# RK809-5.net
KiCad netlist of a schematic drawn in Altium Designer
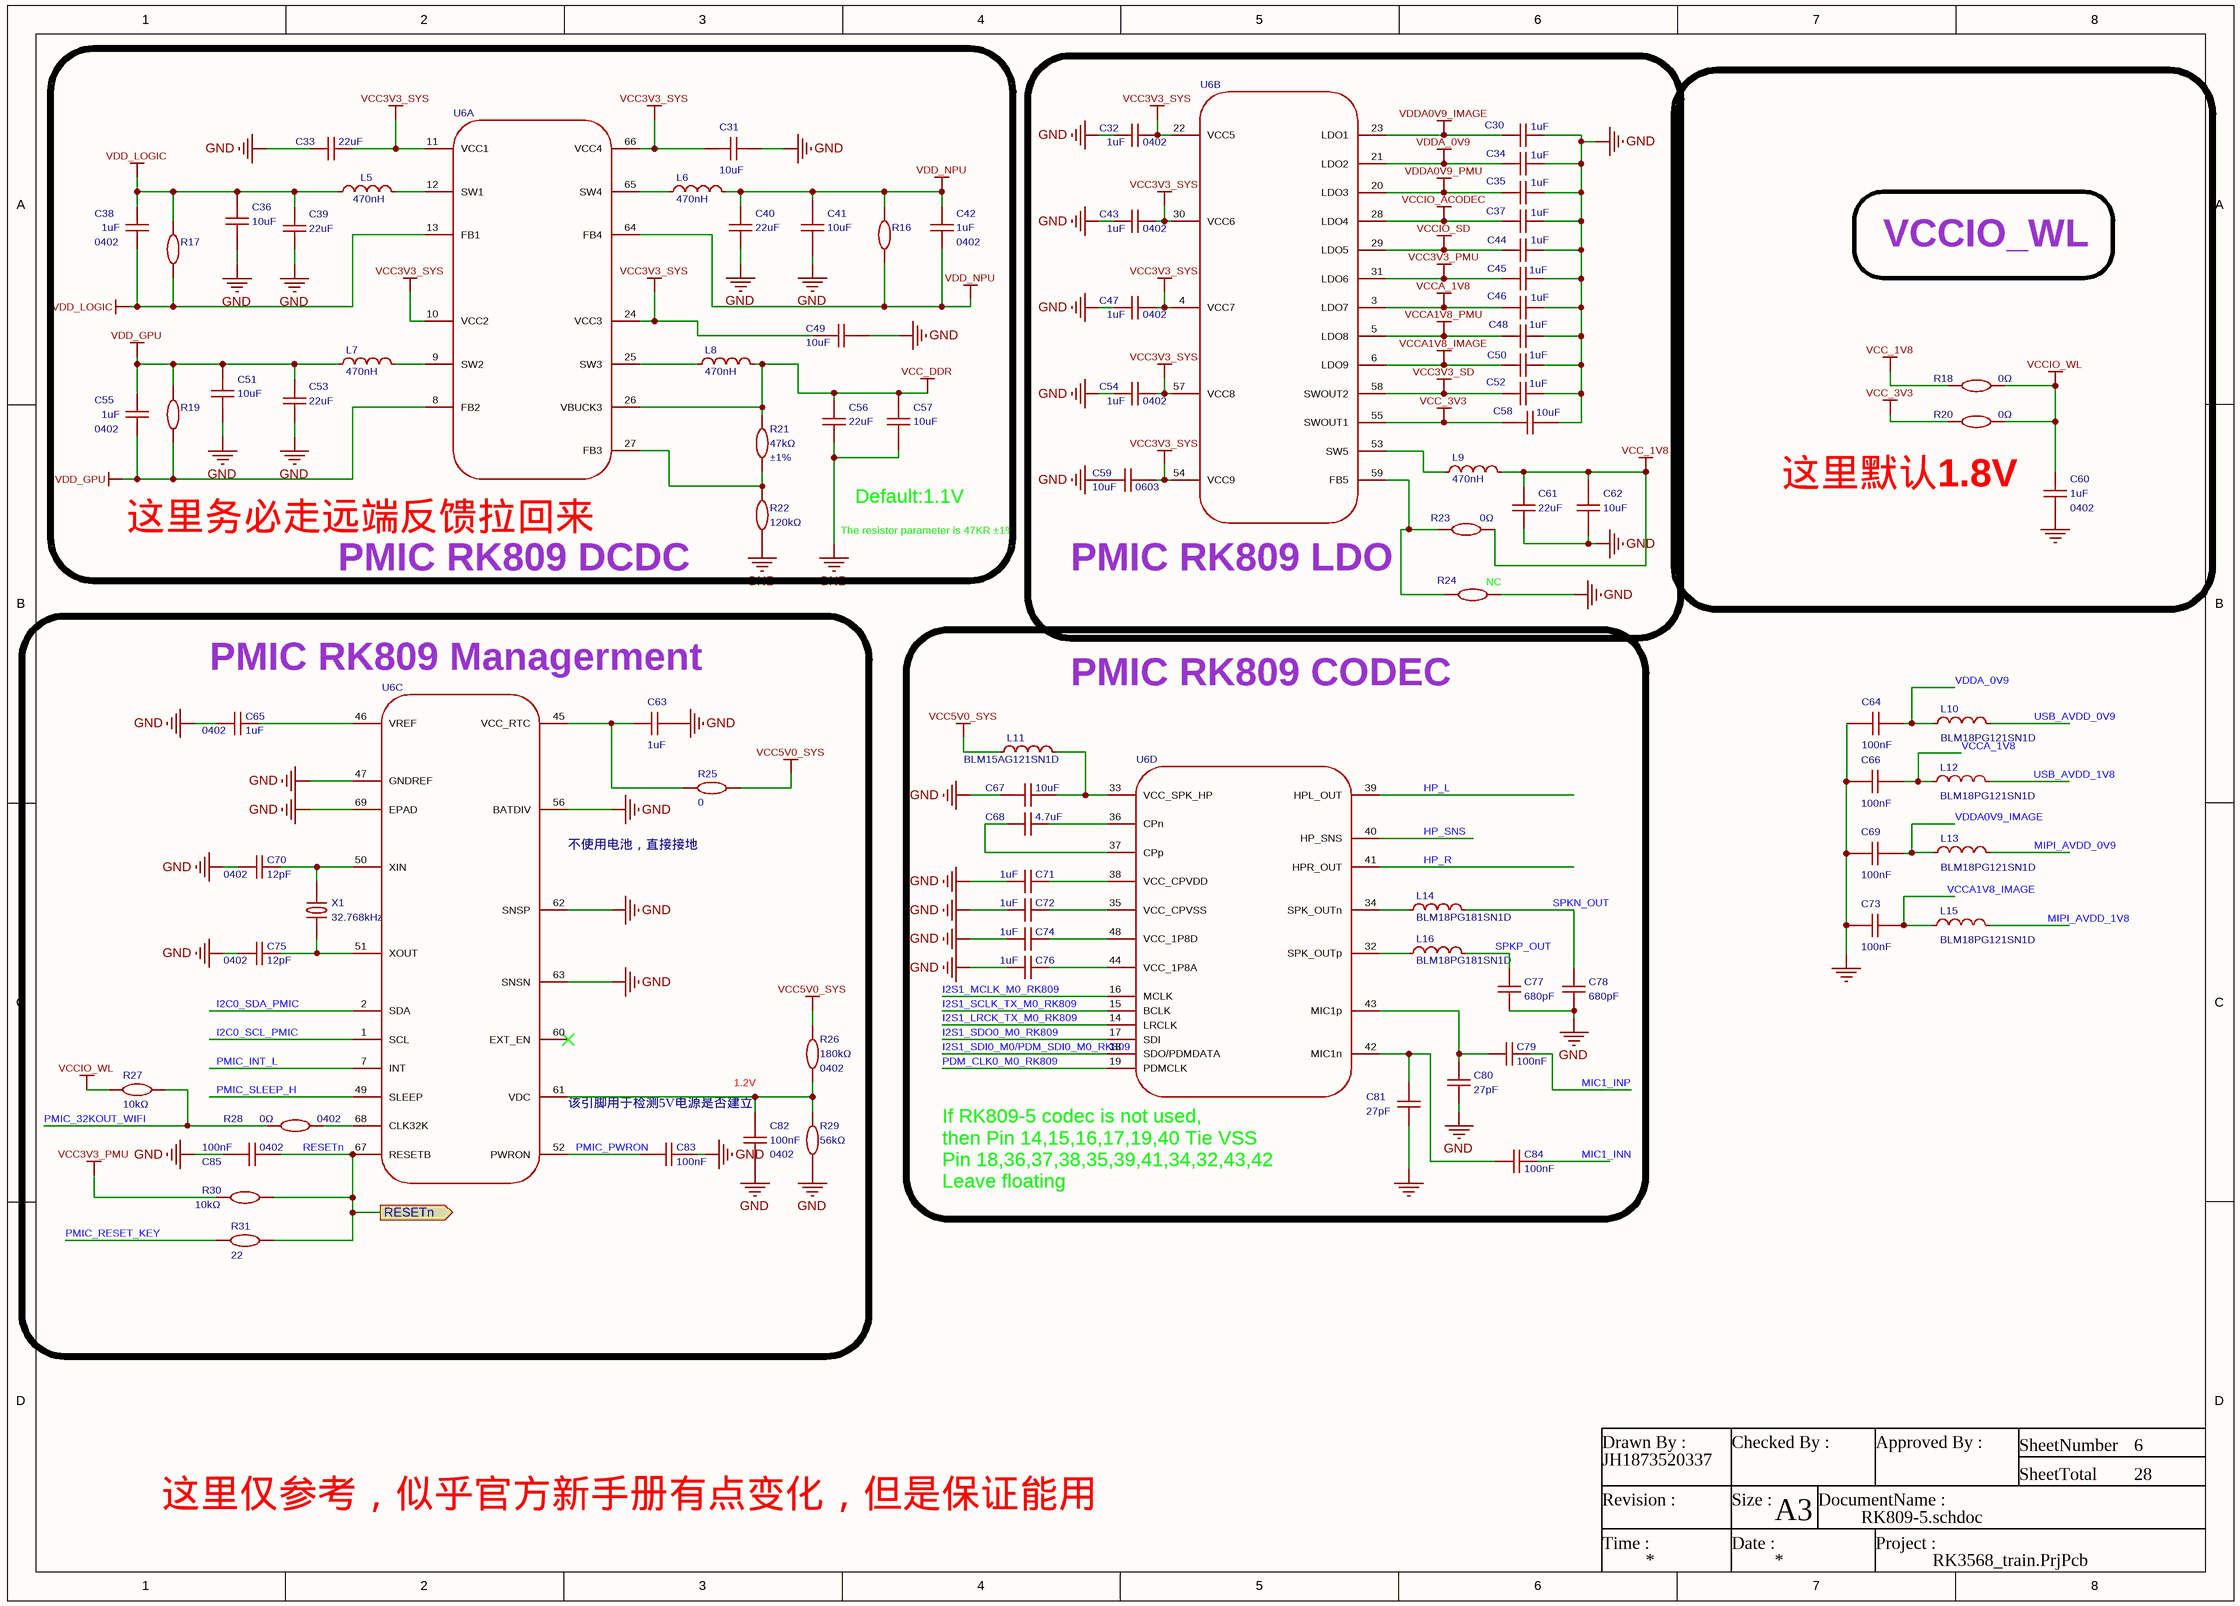
[diagram p0: RK809-5.schdoc]

(export (version "E")
  (design (tool "Eeschema 10.0.6"))
  (components
    (comp (ref "C30")
      (value "1uF")
      (footprint "MYC0402")
      (description "容值:1uF;精度:±10%;额定电压:10V;材质(温度系数):X5R;")
      (fields (field (name "MANUFACTURER") "SAMSUNG(三星)") (field (name "MANUFACTURERPART") "CL05A105KP5NNNC"))
      (libsource (lib "altium-import") (part "root_0_CL05A105KP5NNNC_"))
    )
    (comp (ref "C31")
      (value "10uF")
      (footprint "C0603")
      (libsource (lib "altium-import") (part "root_0_CAP_0603_"))
    )
    (comp (ref "C32")
      (value "1uF")
      (footprint "MYC0402")
      (description "容值:1uF;精度:±10%;额定电压:10V;材质(温度系数):X5R;")
      (fields
        (field (name "SUPPLIER FOOTPRINT") "0402")
        (field (name "MANUFACTURER") "SAMSUNG(三星)")
        (field (name "MANUFACTURERPART") "CL05A105KP5NNNC")
      )
      (libsource (lib "altium-import") (part "root_0_CL05A105KP5NNNC_"))
    )
    (comp (ref "C33")
      (value "22uF")
      (footprint "C0603")
      (description "容值:22uF;精度:±20%;额定电压:6.3V;材质(温度系数):X5R;")
      (fields (field (name "MANUFACTURER") "SAMSUNG(三星)") (field (name "MANUFACTURERPART") "CL10A226MQ8NRNC"))
      (libsource (lib "altium-import") (part "root_0_CL10A226MQ8NRNC_"))
    )
    (comp (ref "C34")
      (value "1uF")
      (footprint "MYC0402")
      (description "容值:1uF;精度:±10%;额定电压:10V;材质(温度系数):X5R;")
      (fields (field (name "MANUFACTURER") "SAMSUNG(三星)") (field (name "MANUFACTURERPART") "CL05A105KP5NNNC"))
      (libsource (lib "altium-import") (part "root_0_CL05A105KP5NNNC_"))
    )
    (comp (ref "C35")
      (value "1uF")
      (footprint "MYC0402")
      (description "容值:1uF;精度:±10%;额定电压:10V;材质(温度系数):X5R;")
      (fields (field (name "MANUFACTURER") "SAMSUNG(三星)") (field (name "MANUFACTURERPART") "CL05A105KP5NNNC"))
      (libsource (lib "altium-import") (part "root_0_CL05A105KP5NNNC_"))
    )
    (comp (ref "C36")
      (value "10uF")
      (footprint "C0603")
      (description "容值:10uF;精度:±10%;额定电压:10V;材质(温度系数):X5R;")
      (fields (field (name "MANUFACTURER") "SAMSUNG(三星)") (field (name "MANUFACTURERPART") "CL10A106KP8NNNC"))
      (libsource (lib "altium-import") (part "root_1_CL10A106KP8NNNC_"))
    )
    (comp (ref "C37")
      (value "1uF")
      (footprint "MYC0402")
      (description "容值:1uF;精度:±10%;额定电压:10V;材质(温度系数):X5R;")
      (fields (field (name "MANUFACTURER") "SAMSUNG(三星)") (field (name "MANUFACTURERPART") "CL05A105KP5NNNC"))
      (libsource (lib "altium-import") (part "root_0_CL05A105KP5NNNC_"))
    )
    (comp (ref "C38")
      (value "1uF")
      (footprint "MYC0402")
      (description "容值:1uF;精度:±10%;额定电压:10V;材质(温度系数):X5R;")
      (fields
        (field (name "SUPPLIER FOOTPRINT") "0402")
        (field (name "MANUFACTURER") "SAMSUNG(三星)")
        (field (name "MANUFACTURERPART") "CL05A105KP5NNNC")
      )
      (libsource (lib "altium-import") (part "root_1_CL05A105KP5NNNC_"))
    )
    (comp (ref "C39")
      (value "22uF")
      (footprint "C0603")
      (description "容值:22uF;精度:±20%;额定电压:6.3V;材质(温度系数):X5R;")
      (fields (field (name "MANUFACTURER") "SAMSUNG(三星)") (field (name "MANUFACTURERPART") "CL10A226MQ8NRNC"))
      (libsource (lib "altium-import") (part "root_3_CL10A226MQ8NRNC_"))
    )
    (comp (ref "C40")
      (value "22uF")
      (footprint "C0603")
      (description "容值:22uF;精度:±20%;额定电压:6.3V;材质(温度系数):X5R;")
      (fields (field (name "MANUFACTURER") "SAMSUNG(三星)") (field (name "MANUFACTURERPART") "CL10A226MQ8NRNC"))
      (libsource (lib "altium-import") (part "root_3_CL10A226MQ8NRNC_"))
    )
    (comp (ref "C41")
      (value "10uF")
      (footprint "C0603")
      (description "容值:10uF;精度:±10%;额定电压:10V;材质(温度系数):X5R;")
      (fields (field (name "MANUFACTURER") "SAMSUNG(三星)") (field (name "MANUFACTURERPART") "CL10A106KP8NNNC"))
      (libsource (lib "altium-import") (part "root_1_CL10A106KP8NNNC_"))
    )
    (comp (ref "C42")
      (value "1uF")
      (footprint "MYC0402")
      (description "容值:1uF;精度:±10%;额定电压:10V;材质(温度系数):X5R;")
      (fields
        (field (name "SUPPLIER FOOTPRINT") "0402")
        (field (name "MANUFACTURER") "SAMSUNG(三星)")
        (field (name "MANUFACTURERPART") "CL05A105KP5NNNC")
      )
      (libsource (lib "altium-import") (part "root_1_CL05A105KP5NNNC_"))
    )
    (comp (ref "C43")
      (value "1uF")
      (footprint "MYC0402")
      (description "容值:1uF;精度:±10%;额定电压:10V;材质(温度系数):X5R;")
      (fields
        (field (name "SUPPLIER FOOTPRINT") "0402")
        (field (name "MANUFACTURER") "SAMSUNG(三星)")
        (field (name "MANUFACTURERPART") "CL05A105KP5NNNC")
      )
      (libsource (lib "altium-import") (part "root_0_CL05A105KP5NNNC_"))
    )
    (comp (ref "C44")
      (value "1uF")
      (footprint "MYC0402")
      (description "容值:1uF;精度:±10%;额定电压:10V;材质(温度系数):X5R;")
      (fields (field (name "MANUFACTURER") "SAMSUNG(三星)") (field (name "MANUFACTURERPART") "CL05A105KP5NNNC"))
      (libsource (lib "altium-import") (part "root_0_CL05A105KP5NNNC_"))
    )
    (comp (ref "C45")
      (value "1uF")
      (footprint "MYC0402")
      (description "容值:1uF;精度:±10%;额定电压:10V;材质(温度系数):X5R;")
      (fields (field (name "MANUFACTURER") "SAMSUNG(三星)") (field (name "MANUFACTURERPART") "CL05A105KP5NNNC"))
      (libsource (lib "altium-import") (part "root_0_CL05A105KP5NNNC_"))
    )
    (comp (ref "C46")
      (value "1uF")
      (footprint "MYC0402")
      (description "容值:1uF;精度:±10%;额定电压:10V;材质(温度系数):X5R;")
      (fields (field (name "MANUFACTURER") "SAMSUNG(三星)") (field (name "MANUFACTURERPART") "CL05A105KP5NNNC"))
      (libsource (lib "altium-import") (part "root_0_CL05A105KP5NNNC_"))
    )
    (comp (ref "C47")
      (value "1uF")
      (footprint "MYC0402")
      (description "容值:1uF;精度:±10%;额定电压:10V;材质(温度系数):X5R;")
      (fields
        (field (name "SUPPLIER FOOTPRINT") "0402")
        (field (name "MANUFACTURER") "SAMSUNG(三星)")
        (field (name "MANUFACTURERPART") "CL05A105KP5NNNC")
      )
      (libsource (lib "altium-import") (part "root_0_CL05A105KP5NNNC_"))
    )
    (comp (ref "C48")
      (value "1uF")
      (footprint "MYC0402")
      (description "容值:1uF;精度:±10%;额定电压:10V;材质(温度系数):X5R;")
      (fields (field (name "MANUFACTURER") "SAMSUNG(三星)") (field (name "MANUFACTURERPART") "CL05A105KP5NNNC"))
      (libsource (lib "altium-import") (part "root_0_CL05A105KP5NNNC_"))
    )
    (comp (ref "C49")
      (value "10uF")
      (footprint "C0603")
      (description "容值:10uF;精度:±10%;额定电压:10V;材质(温度系数):X5R;")
      (fields (field (name "MANUFACTURER") "SAMSUNG(三星)") (field (name "MANUFACTURERPART") "CL10A106KP8NNNC"))
      (libsource (lib "altium-import") (part "root_2_CL10A106KP8NNNC_"))
    )
    (comp (ref "C50")
      (value "1uF")
      (footprint "MYC0402")
      (description "容值:1uF;精度:±10%;额定电压:10V;材质(温度系数):X5R;")
      (fields (field (name "MANUFACTURER") "SAMSUNG(三星)") (field (name "MANUFACTURERPART") "CL05A105KP5NNNC"))
      (libsource (lib "altium-import") (part "root_0_CL05A105KP5NNNC_"))
    )
    (comp (ref "C51")
      (value "10uF")
      (footprint "C0603")
      (description "容值:10uF;精度:±10%;额定电压:10V;材质(温度系数):X5R;")
      (fields (field (name "MANUFACTURER") "SAMSUNG(三星)") (field (name "MANUFACTURERPART") "CL10A106KP8NNNC"))
      (libsource (lib "altium-import") (part "root_1_CL10A106KP8NNNC_"))
    )
    (comp (ref "C52")
      (value "1uF")
      (footprint "MYC0402")
      (description "容值:1uF;精度:±10%;额定电压:10V;材质(温度系数):X5R;")
      (fields (field (name "MANUFACTURER") "SAMSUNG(三星)") (field (name "MANUFACTURERPART") "CL05A105KP5NNNC"))
      (libsource (lib "altium-import") (part "root_0_CL05A105KP5NNNC_"))
    )
    (comp (ref "C53")
      (value "22uF")
      (footprint "C0603")
      (description "容值:22uF;精度:±20%;额定电压:6.3V;材质(温度系数):X5R;")
      (fields (field (name "MANUFACTURER") "SAMSUNG(三星)") (field (name "MANUFACTURERPART") "CL10A226MQ8NRNC"))
      (libsource (lib "altium-import") (part "root_3_CL10A226MQ8NRNC_"))
    )
    (comp (ref "C54")
      (value "1uF")
      (footprint "MYC0402")
      (description "容值:1uF;精度:±10%;额定电压:10V;材质(温度系数):X5R;")
      (fields
        (field (name "SUPPLIER FOOTPRINT") "0402")
        (field (name "MANUFACTURER") "SAMSUNG(三星)")
        (field (name "MANUFACTURERPART") "CL05A105KP5NNNC")
      )
      (libsource (lib "altium-import") (part "root_0_CL05A105KP5NNNC_"))
    )
    (comp (ref "C55")
      (value "1uF")
      (footprint "MYC0402")
      (description "容值:1uF;精度:±10%;额定电压:10V;材质(温度系数):X5R;")
      (fields
        (field (name "SUPPLIER FOOTPRINT") "0402")
        (field (name "MANUFACTURER") "SAMSUNG(三星)")
        (field (name "MANUFACTURERPART") "CL05A105KP5NNNC")
      )
      (libsource (lib "altium-import") (part "root_1_CL05A105KP5NNNC_"))
    )
    (comp (ref "C56")
      (value "22uF")
      (footprint "C0603")
      (description "容值:22uF;精度:±20%;额定电压:6.3V;材质(温度系数):X5R;")
      (fields (field (name "MANUFACTURER") "SAMSUNG(三星)") (field (name "MANUFACTURERPART") "CL10A226MQ8NRNC"))
      (libsource (lib "altium-import") (part "root_3_CL10A226MQ8NRNC_"))
    )
    (comp (ref "C57")
      (value "10uF")
      (footprint "C0603")
      (description "容值:10uF;精度:±10%;额定电压:10V;材质(温度系数):X5R;")
      (fields (field (name "MANUFACTURER") "SAMSUNG(三星)") (field (name "MANUFACTURERPART") "CL10A106KP8NNNC"))
      (libsource (lib "altium-import") (part "root_1_CL10A106KP8NNNC_"))
    )
    (comp (ref "C58")
      (value "10uF")
      (footprint "C0603")
      (description "容值:10uF;精度:±10%;额定电压:10V;材质(温度系数):X5R;")
      (fields (field (name "MANUFACTURER") "SAMSUNG(三星)") (field (name "MANUFACTURERPART") "CL10A106KP8NNNC"))
      (libsource (lib "altium-import") (part "root_0_CL10A106KP8NNNC_"))
    )
    (comp (ref "C59")
      (value "10uF")
      (footprint "C0603")
      (description "容值:10uF;精度:±10%;额定电压:10V;材质(温度系数):X5R;")
      (fields
        (field (name "SUPPLIER FOOTPRINT") "0603")
        (field (name "MANUFACTURER") "SAMSUNG(三星)")
        (field (name "MANUFACTURERPART") "CL10A106KP8NNNC")
      )
      (libsource (lib "altium-import") (part "root_0_CL10A106KP8NNNC_"))
    )
    (comp (ref "C60")
      (value "1uF")
      (footprint "MYC0402")
      (description "容值:1uF;精度:±10%;额定电压:10V;材质(温度系数):X5R;")
      (fields
        (field (name "SUPPLIER FOOTPRINT") "0402")
        (field (name "MANUFACTURER") "SAMSUNG(三星)")
        (field (name "MANUFACTURERPART") "CL05A105KP5NNNC")
      )
      (libsource (lib "altium-import") (part "root_1_CL05A105KP5NNNC_"))
    )
    (comp (ref "C61")
      (value "22uF")
      (footprint "C0603")
      (description "容值:22uF;精度:±20%;额定电压:6.3V;材质(温度系数):X5R;")
      (fields (field (name "MANUFACTURER") "SAMSUNG(三星)") (field (name "MANUFACTURERPART") "CL10A226MQ8NRNC"))
      (libsource (lib "altium-import") (part "root_3_CL10A226MQ8NRNC_"))
    )
    (comp (ref "C62")
      (value "10uF")
      (footprint "C0603")
      (description "容值:10uF;精度:±10%;额定电压:10V;材质(温度系数):X5R;")
      (fields (field (name "MANUFACTURER") "SAMSUNG(三星)") (field (name "MANUFACTURERPART") "CL10A106KP8NNNC"))
      (libsource (lib "altium-import") (part "root_1_CL10A106KP8NNNC_"))
    )
    (comp (ref "C63")
      (value "1uF")
      (footprint "MYC0402")
      (description "容值:1uF;精度:±10%;额定电压:10V;材质(温度系数):X5R;")
      (fields (field (name "MANUFACTURER") "SAMSUNG(三星)") (field (name "MANUFACTURERPART") "CL05A105KP5NNNC"))
      (libsource (lib "altium-import") (part "root_0_CL05A105KP5NNNC_"))
    )
    (comp (ref "C64")
      (value "100nF")
      (footprint "MYC0402")
      (libsource (lib "altium-import") (part "root_0_CAP_0402_"))
    )
    (comp (ref "C65")
      (value "1uF")
      (footprint "MYC0402")
      (description "容值:1uF;精度:±10%;额定电压:10V;材质(温度系数):X5R;")
      (fields
        (field (name "SUPPLIER FOOTPRINT") "0402")
        (field (name "MANUFACTURER") "SAMSUNG(三星)")
        (field (name "MANUFACTURERPART") "CL05A105KP5NNNC")
      )
      (libsource (lib "altium-import") (part "root_0_CL05A105KP5NNNC_"))
    )
    (comp (ref "C66")
      (value "100nF")
      (footprint "MYC0402")
      (libsource (lib "altium-import") (part "root_0_CAP_0402_"))
    )
    (comp (ref "C67")
      (value "10uF")
      (footprint "MYC0402")
      (description "容值:10uF;精度:±20%;额定电压:6.3V;材质(温度系数):X5R;")
      (fields (field (name "MANUFACTURER") "SAMSUNG(三星)") (field (name "MANUFACTURERPART") "CL05A106MQ5NUNC"))
      (libsource (lib "altium-import") (part "root_0_CL05A106MQ5NUNC_"))
    )
    (comp (ref "C68")
      (value "4.7uF")
      (footprint "MYC0402")
      (description "容值:4.7uF;精度:±20%;额定电压:6.3V;材质(温度系数):X5R;")
      (fields (field (name "MANUFACTURER") "SAMSUNG(三星)") (field (name "MANUFACTURERPART") "CL05A475MQ5NRNC"))
      (libsource (lib "altium-import") (part "root_2_CL05A475MQ5NRNC_"))
    )
    (comp (ref "C69")
      (value "100nF")
      (footprint "MYC0402")
      (libsource (lib "altium-import") (part "root_0_CAP_0402_"))
    )
    (comp (ref "C70")
      (value "12pF")
      (footprint "MYC0402")
      (description "容值:12pF;精度:±5%;额定电压:50V;材质(温度系数):C0G;")
      (fields
        (field (name "SUPPLIER FOOTPRINT") "0402")
        (field (name "MANUFACTURER") "FH(风华)")
        (field (name "MANUFACTURERPART") "0402CG120J500NT")
      )
      (libsource (lib "altium-import") (part "root_0_0402CG120J500NT_"))
    )
    (comp (ref "C71")
      (value "1uF")
      (footprint "MYC0402")
      (description "容值:1uF;精度:±10%;额定电压:10V;材质(温度系数):X5R;")
      (fields (field (name "MANUFACTURER") "SAMSUNG(三星)") (field (name "MANUFACTURERPART") "CL05A105KP5NNNC"))
      (libsource (lib "altium-import") (part "root_0_CL05A105KP5NNNC_"))
    )
    (comp (ref "C72")
      (value "1uF")
      (footprint "MYC0402")
      (description "容值:1uF;精度:±10%;额定电压:10V;材质(温度系数):X5R;")
      (fields (field (name "MANUFACTURER") "SAMSUNG(三星)") (field (name "MANUFACTURERPART") "CL05A105KP5NNNC"))
      (libsource (lib "altium-import") (part "root_0_CL05A105KP5NNNC_"))
    )
    (comp (ref "C73")
      (value "100nF")
      (footprint "MYC0402")
      (libsource (lib "altium-import") (part "root_0_CAP_0402_"))
    )
    (comp (ref "C74")
      (value "1uF")
      (footprint "MYC0402")
      (description "容值:1uF;精度:±10%;额定电压:10V;材质(温度系数):X5R;")
      (fields (field (name "MANUFACTURER") "SAMSUNG(三星)") (field (name "MANUFACTURERPART") "CL05A105KP5NNNC"))
      (libsource (lib "altium-import") (part "root_0_CL05A105KP5NNNC_"))
    )
    (comp (ref "C75")
      (value "12pF")
      (footprint "MYC0402")
      (description "容值:12pF;精度:±5%;额定电压:50V;材质(温度系数):C0G;")
      (fields
        (field (name "SUPPLIER FOOTPRINT") "0402")
        (field (name "MANUFACTURER") "FH(风华)")
        (field (name "MANUFACTURERPART") "0402CG120J500NT")
      )
      (libsource (lib "altium-import") (part "root_2_0402CG120J500NT_"))
    )
    (comp (ref "C76")
      (value "1uF")
      (footprint "MYC0402")
      (description "容值:1uF;精度:±10%;额定电压:10V;材质(温度系数):X5R;")
      (fields (field (name "MANUFACTURER") "SAMSUNG(三星)") (field (name "MANUFACTURERPART") "CL05A105KP5NNNC"))
      (libsource (lib "altium-import") (part "root_0_CL05A105KP5NNNC_"))
    )
    (comp (ref "C77")
      (value "680pF")
      (footprint "R0402")
      (description "容值:680pF;精度:±10%;额定电压:50V;材质(温度系数):X7R;")
      (fields (field (name "MANUFACTURER") "FH(风华)") (field (name "MANUFACTURERPART") "0402B681K500NT"))
      (libsource (lib "altium-import") (part "root_1_0402B681K500NT_"))
    )
    (comp (ref "C78")
      (value "680pF")
      (footprint "R0402")
      (description "容值:680pF;精度:±10%;额定电压:50V;材质(温度系数):X7R;")
      (fields (field (name "MANUFACTURER") "FH(风华)") (field (name "MANUFACTURERPART") "0402B681K500NT"))
      (libsource (lib "altium-import") (part "root_1_0402B681K500NT_"))
    )
    (comp (ref "C79")
      (value "100nF")
      (footprint "MYC0402")
      (description "容值:100nF;精度:±10%;额定电压:16V;材质(温度系数):X7R;")
      (fields (field (name "MANUFACTURER") "SAMSUNG(三星)") (field (name "MANUFACTURERPART") "CL05B104KO5NNNC"))
      (libsource (lib "altium-import") (part "root_0_CL05B104KO5NNNC_"))
    )
    (comp (ref "C80")
      (value "27pF")
      (footprint "R0402")
      (description "容值:27pF;精度:±5%;额定电压:50V;材质(温度系数):C0G;")
      (fields (field (name "MANUFACTURER") "FH(风华)") (field (name "MANUFACTURERPART") "0402CG270J500NT"))
      (libsource (lib "altium-import") (part "root_1_0402CG270J500NT_"))
    )
    (comp (ref "C81")
      (value "27pF")
      (footprint "R0402")
      (description "容值:27pF;精度:±5%;额定电压:50V;材质(温度系数):C0G;")
      (fields (field (name "MANUFACTURER") "FH(风华)") (field (name "MANUFACTURERPART") "0402CG270J500NT"))
      (libsource (lib "altium-import") (part "root_1_0402CG270J500NT_"))
    )
    (comp (ref "C82")
      (value "100nF")
      (footprint "MYC0402")
      (description "容值:100nF;精度:±10%;额定电压:50V;材质(温度系数):X7R;")
      (fields
        (field (name "SUPPLIER FOOTPRINT") "0402")
        (field (name "MANUFACTURER") "SAMSUNG(三星)")
        (field (name "MANUFACTURERPART") "CL05B104KB54PNC")
      )
      (libsource (lib "altium-import") (part "root_1_CL05B104KB54PNC_"))
    )
    (comp (ref "C83")
      (value "100nF")
      (footprint "MYC0402")
      (description "容值:100nF;精度:±10%;额定电压:50V;材质(温度系数):X7R;")
      (fields (field (name "MANUFACTURER") "SAMSUNG(三星)") (field (name "MANUFACTURERPART") "CL05B104KB54PNC"))
      (libsource (lib "altium-import") (part "root_0_CL05B104KB54PNC_"))
    )
    (comp (ref "C84")
      (value "100nF")
      (footprint "MYC0402")
      (description "容值:100nF;精度:±10%;额定电压:16V;材质(温度系数):X7R;")
      (fields (field (name "MANUFACTURER") "SAMSUNG(三星)") (field (name "MANUFACTURERPART") "CL05B104KO5NNNC"))
      (libsource (lib "altium-import") (part "root_0_CL05B104KO5NNNC_"))
    )
    (comp (ref "C85")
      (value "100nF")
      (footprint "MYC0402")
      (description "容值:100nF;精度:±10%;额定电压:50V;材质(温度系数):X7R;")
      (fields
        (field (name "SUPPLIER FOOTPRINT") "0402")
        (field (name "MANUFACTURER") "SAMSUNG(三星)")
        (field (name "MANUFACTURERPART") "CL05B104KB54PNC")
      )
      (libsource (lib "altium-import") (part "root_0_CL05B104KB54PNC_"))
    )
    (comp (ref "L5")
      (value "470nH")
      (footprint "IND-SMD_L2.0-W1.6_MHCHL201610A-1R0M-Q8A")
      (description "电感值:470nH;精度:±20%;额定电流:4.05A;")
      (fields (field (name "MANUFACTURER") "PSA(信昌电陶)") (field (name "MANUFACTURERPART") "MCS20FC-R47MHC"))
      (libsource (lib "altium-import") (part "root_0_MCS20FC-R47MHC_"))
    )
    (comp (ref "L6")
      (value "470nH")
      (footprint "IND-SMD_L2.0-W1.6_MHCHL201610A-1R0M-Q8A")
      (description "电感值:470nH;精度:±20%;额定电流:4.05A;")
      (fields (field (name "MANUFACTURER") "PSA(信昌电陶)") (field (name "MANUFACTURERPART") "MCS20FC-R47MHC"))
      (libsource (lib "altium-import") (part "root_0_MCS20FC-R47MHC_"))
    )
    (comp (ref "L7")
      (value "470nH")
      (footprint "IND-SMD_L2.0-W1.6_MHCHL201610A-1R0M-Q8A")
      (description "电感值:470nH;精度:±20%;额定电流:4.05A;")
      (fields (field (name "MANUFACTURER") "PSA(信昌电陶)") (field (name "MANUFACTURERPART") "MCS20FC-R47MHC"))
      (libsource (lib "altium-import") (part "root_0_MCS20FC-R47MHC_"))
    )
    (comp (ref "L8")
      (value "470nH")
      (footprint "IND-SMD_L2.0-W1.6_MHCHL201610A-1R0M-Q8A")
      (description "电感值:470nH;精度:±20%;额定电流:4.05A;")
      (fields (field (name "MANUFACTURER") "PSA(信昌电陶)") (field (name "MANUFACTURERPART") "MCS20FC-R47MHC"))
      (libsource (lib "altium-import") (part "root_0_MCS20FC-R47MHC_"))
    )
    (comp (ref "L9")
      (value "470nH")
      (footprint "IND-SMD_L2.0-W1.6_MHCHL201610A-1R0M-Q8A")
      (description "电感值:470nH;精度:±20%;额定电流:4.05A;")
      (fields (field (name "MANUFACTURER") "PSA(信昌电陶)") (field (name "MANUFACTURERPART") "MCS20FC-R47MHC"))
      (libsource (lib "altium-import") (part "root_0_MCS20FC-R47MHC_"))
    )
    (comp (ref "L10")
      (value "BLM18PG121SN1D")
      (footprint "L0603")
      (description "标称阻抗@测试频率:120Ω@100MHz;误差:±25%;直流电阻(RDC):50mΩ;")
      (fields (field (name "MANUFACTURER") "muRata(村田)") (field (name "TOLERANCE") "±25%"))
      (libsource (lib "altium-import") (part "root_0_BLM18PG121SN1D_"))
    )
    (comp (ref "L11")
      (value "BLM15AG121SN1D")
      (footprint "L0402")
      (description "标称阻抗@测试频率:120Ω@100MHz;误差:±25%;直流电阻(RDC):250mΩ;额定电流:500mA;电路数:1;")
      (fields (field (name "MANUFACTURER") "muRata(村田)") (field (name "TOLERANCE") "±25%"))
      (libsource (lib "altium-import") (part "root_0_BLM15AG121SN1D_"))
    )
    (comp (ref "L12")
      (value "BLM18PG121SN1D")
      (footprint "L0603")
      (description "标称阻抗@测试频率:120Ω@100MHz;误差:±25%;直流电阻(RDC):50mΩ;")
      (fields (field (name "MANUFACTURER") "muRata(村田)") (field (name "TOLERANCE") "±25%"))
      (libsource (lib "altium-import") (part "root_0_BLM18PG121SN1D_"))
    )
    (comp (ref "L13")
      (value "BLM18PG121SN1D")
      (footprint "L0603")
      (description "标称阻抗@测试频率:120Ω@100MHz;误差:±25%;直流电阻(RDC):50mΩ;")
      (fields (field (name "MANUFACTURER") "muRata(村田)") (field (name "TOLERANCE") "±25%"))
      (libsource (lib "altium-import") (part "root_0_BLM18PG121SN1D_"))
    )
    (comp (ref "L14")
      (value "BLM18PG181SN1D")
      (footprint "L0603")
      (description "标称阻抗@测试频率:180Ω@100MHz;误差:±25%;直流电阻(RDC):90mΩ;额定电流:1.5A;电路数:1;")
      (fields (field (name "MANUFACTURER") "muRata(村田)") (field (name "TOLERANCE") "±25%"))
      (libsource (lib "altium-import") (part "root_0_BLM18PG181SN1D_"))
    )
    (comp (ref "L15")
      (value "BLM18PG121SN1D")
      (footprint "L0603")
      (description "标称阻抗@测试频率:120Ω@100MHz;误差:±25%;直流电阻(RDC):50mΩ;")
      (fields (field (name "MANUFACTURER") "muRata(村田)") (field (name "TOLERANCE") "±25%"))
      (libsource (lib "altium-import") (part "root_0_BLM18PG121SN1D_"))
    )
    (comp (ref "L16")
      (value "BLM18PG181SN1D")
      (footprint "L0603")
      (description "标称阻抗@测试频率:180Ω@100MHz;误差:±25%;直流电阻(RDC):90mΩ;额定电流:1.5A;电路数:1;")
      (fields (field (name "MANUFACTURER") "muRata(村田)") (field (name "TOLERANCE") "±25%"))
      (libsource (lib "altium-import") (part "root_0_BLM18PG181SN1D_"))
    )
    (comp (ref "R16")
      (value "0402WGF1000TCE")
      (footprint "R0402")
      (fields (field (name "MANUFACTURER") "UNI-ROYAL(厚声)"))
      (libsource (lib "altium-import") (part "root_1_0402WGF1000TCE_"))
    )
    (comp (ref "R17")
      (value "0402WGF1000TCE")
      (footprint "R0402")
      (fields (field (name "MANUFACTURER") "UNI-ROYAL(厚声)"))
      (libsource (lib "altium-import") (part "root_1_0402WGF1000TCE_"))
    )
    (comp (ref "R18")
      (value "0Ω")
      (footprint "R0402")
      (description "电阻类型:-;阻值:0Ω;功率:100mW;温度系数:-100ppm/℃~+600ppm/℃;最大工作电压:-;工作温度范围:-55℃~+155℃;")
      (fields (field (name "MANUFACTURER") "PANASONIC(松下)") (field (name "MANUFACTURERPART") "ERJ2GE0R00X"))
      (libsource (lib "altium-import") (part "root_0_ERJ2GE0R00X_"))
    )
    (comp (ref "R19")
      (value "0402WGF1000TCE")
      (footprint "R0402")
      (fields (field (name "MANUFACTURER") "UNI-ROYAL(厚声)"))
      (libsource (lib "altium-import") (part "root_1_0402WGF1000TCE_"))
    )
    (comp (ref "R20")
      (value "0Ω")
      (footprint "R0402")
      (description "电阻类型:-;阻值:0Ω;功率:100mW;温度系数:-100ppm/℃~+600ppm/℃;最大工作电压:-;工作温度范围:-55℃~+155℃;")
      (fields (field (name "MANUFACTURER") "PANASONIC(松下)") (field (name "MANUFACTURERPART") "ERJ2GE0R00X"))
      (libsource (lib "altium-import") (part "root_0_ERJ2GE0R00X_"))
    )
    (comp (ref "R21")
      (value "47kΩ")
      (footprint "R0402")
      (description "电阻类型:厚膜电阻;阻值:47kΩ;精度:±1%;功率:62.5mW;温度系数:±100ppm/℃;最大工作电压:50V;工作温度范围:-55℃~+155℃;")
      (fields
        (field (name "TOLERANCE") "±1%")
        (field (name "MANUFACTURER") "UNI-ROYAL(厚声)")
        (field (name "MANUFACTURERPART") "0402WGF4702TCE")
      )
      (libsource (lib "altium-import") (part "root_3_0402WGF4702TCE_"))
    )
    (comp (ref "R22")
      (value "120kΩ")
      (footprint "R0402")
      (description "电阻类型:厚膜电阻;阻值:120kΩ;精度:±1%;功率:62.5mW;温度系数:±100ppm/℃;最大工作电压:50V;工作温度范围:-55℃~+155℃;")
      (fields
        (field (name "MANUFACTURER") "UNI-ROYAL(厚声)")
        (field (name "MANUFACTURERPART") "0402WGF1203TCE")
      )
      (libsource (lib "altium-import") (part "root_1_0402WGF1203TCE_"))
    )
    (comp (ref "R23")
      (value "0Ω")
      (footprint "R0402")
      (description "电阻类型:-;阻值:0Ω;功率:100mW;温度系数:-100ppm/℃~+600ppm/℃;最大工作电压:-;工作温度范围:-55℃~+155℃;")
      (fields (field (name "MANUFACTURER") "PANASONIC(松下)") (field (name "MANUFACTURERPART") "ERJ2GE0R00X"))
      (libsource (lib "altium-import") (part "root_0_ERJ2GE0R00X_"))
    )
    (comp (ref "R24")
      (value "NC")
      (footprint "R0402")
      (description "电阻类型:-;阻值:0Ω;功率:100mW;温度系数:-100ppm/℃~+600ppm/℃;最大工作电压:-;工作温度范围:-55℃~+155℃;")
      (fields (field (name "MANUFACTURER") "PANASONIC(松下)") (field (name "MANUFACTURERPART") "ERJ2GE0R00X"))
      (libsource (lib "altium-import") (part "root_0_ERJ2GE0R00X_"))
    )
    (comp (ref "R25")
      (value "0")
      (footprint "R0402")
      (libsource (lib "altium-import") (part "root_0_Res_0402_"))
    )
    (comp (ref "R26")
      (value "180kΩ")
      (footprint "R0402")
      (description "电阻类型:厚膜电阻;阻值:180kΩ;精度:±1%;功率:62.5mW;温度系数:±100ppm/℃;最大工作电压:50V;工作温度范围:-55℃~+155℃;")
      (fields
        (field (name "SUPPLIER FOOTPRINT") "0402")
        (field (name "MANUFACTURER") "YAGEO(国巨)")
        (field (name "MANUFACTURERPART") "RC0402FR-07180KL")
      )
      (libsource (lib "altium-import") (part "root_1_RC0402FR-07180KL_"))
    )
    (comp (ref "R27")
      (value "10kΩ")
      (footprint "R0402")
      (description "电阻类型:厚膜电阻;阻值:10kΩ;精度:±1%;功率:63mW;温度系数:±100ppm/K;最大工作电压:50V;工作温度范围:-55℃~+155℃;")
      (fields (field (name "MANUFACTURER") "VISHAY(威世)") (field (name "MANUFACTURERPART") "CRCW040210K0FKED"))
      (libsource (lib "altium-import") (part "root_0_CRCW040210K0FKED_"))
    )
    (comp (ref "R28")
      (value "0Ω")
      (footprint "R0402")
      (description "电阻类型:-;阻值:0Ω;功率:100mW;温度系数:-100ppm/℃~+600ppm/℃;最大工作电压:-;工作温度范围:-55℃~+155℃;")
      (fields
        (field (name "SUPPLIER FOOTPRINT") "0402")
        (field (name "MANUFACTURER") "PANASONIC(松下)")
        (field (name "MANUFACTURERPART") "ERJ2GE0R00X")
      )
      (libsource (lib "altium-import") (part "root_0_ERJ2GE0R00X_"))
    )
    (comp (ref "R29")
      (value "56kΩ")
      (footprint "R0402")
      (description "精度:±1%;功率:1/16W;温度系数:±100ppm/℃;阻值:56kΩ;最大工作电压:50V;工作温度范围:-55℃~+155℃;")
      (fields
        (field (name "MANUFACTURER") "UNI-ROYAL(厚声)")
        (field (name "MANUFACTURERPART") "0402WGF5602TCE")
      )
      (libsource (lib "altium-import") (part "root_1_0402WGF5602TCE_"))
    )
    (comp (ref "R30")
      (value "10kΩ")
      (footprint "R0402")
      (description "电阻类型:厚膜电阻;阻值:10kΩ;精度:±1%;功率:63mW;温度系数:±100ppm/K;最大工作电压:50V;工作温度范围:-55℃~+155℃;")
      (fields (field (name "MANUFACTURER") "VISHAY(威世)") (field (name "MANUFACTURERPART") "CRCW040210K0FKED"))
      (libsource (lib "altium-import") (part "root_0_CRCW040210K0FKED_"))
    )
    (comp (ref "R31")
      (value "22")
      (footprint "R0402")
      (libsource (lib "altium-import") (part "root_0_Res_0402_"))
    )
    (comp (ref "U6")
      (value "~")
      (footprint "RK809-5")
      (libsource (lib "altium-import") (part "root_0_RK809-5_"))
    )
    (comp (ref "X1")
      (value "32.768kHz")
      (footprint "CRYSTAL-SMD_L3.2-W1.5-1")
      (description "频率:32.768kHz;频率公差:±20ppm;负载电容:12.5pF;")
      (fields (field (name "MANUFACTURER") "YXC(扬兴晶振)") (field (name "MANUFACTURERPART") "XKXGI-SUA-32.768K"))
      (libsource (lib "altium-import") (part "root_1_XKXGI-SUA-32.768K_"))
    )
  )
  (nets
    (net (code "1") (name "/HP_L") (class "Default")
      (node (ref "U6") (pin "39") (pinfunction "HPL_OUT_39") (pintype "passive"))
    )
    (net (code "2") (name "/HP_R") (class "Default")
      (node (ref "U6") (pin "41") (pinfunction "HPR_OUT_41") (pintype "passive"))
    )
    (net (code "3") (name "/HP_SNS") (class "Default")
      (node (ref "U6") (pin "40") (pinfunction "HP_SNS_40") (pintype "passive"))
    )
    (net (code "4") (name "/I2C0_SCL_PMIC") (class "Default")
      (node (ref "U6") (pin "1") (pinfunction "SCL_1") (pintype "passive"))
    )
    (net (code "5") (name "/I2C0_SDA_PMIC") (class "Default")
      (node (ref "U6") (pin "2") (pinfunction "SDA_2") (pintype "passive"))
    )
    (net (code "6") (name "/I2S1_LRCK_TX_M0_RK809") (class "Default")
      (node (ref "U6") (pin "14") (pinfunction "LRCLK_14") (pintype "passive"))
    )
    (net (code "7") (name "/I2S1_MCLK_M0_RK809") (class "Default")
      (node (ref "U6") (pin "16") (pinfunction "MCLK_16") (pintype "passive"))
    )
    (net (code "8") (name "/I2S1_SCLK_TX_M0_RK809") (class "Default")
      (node (ref "U6") (pin "15") (pinfunction "BCLK_15") (pintype "passive"))
    )
    (net (code "9") (name "/I2S1_SDI0_M0{slash}PDM_SDI0_M0_RK809") (class "Default")
      (node (ref "U6") (pin "18") (pinfunction "SDO/PDMDATA_18") (pintype "passive"))
    )
    (net (code "10") (name "/I2S1_SDO0_M0_RK809") (class "Default")
      (node (ref "U6") (pin "17") (pinfunction "SDI_17") (pintype "passive"))
    )
    (net (code "11") (name "/MIC1_INN") (class "Default")
      (node (ref "C84") (pin "2") (pinfunction "2_2") (pintype "passive"))
    )
    (net (code "12") (name "/MIC1_INP") (class "Default")
      (node (ref "C79") (pin "2") (pinfunction "2_2") (pintype "passive"))
    )
    (net (code "13") (name "/MIPI_AVDD_0V9") (class "Default")
      (node (ref "L13") (pin "2") (pinfunction "2_2") (pintype "passive"))
    )
    (net (code "14") (name "/MIPI_AVDD_1V8") (class "Default")
      (node (ref "L15") (pin "2") (pinfunction "2_2") (pintype "passive"))
    )
    (net (code "15") (name "/PDM_CLK0_M0_RK809") (class "Default")
      (node (ref "U6") (pin "19") (pinfunction "PDMCLK_19") (pintype "passive"))
    )
    (net (code "16") (name "/PMIC_32KOUT_WIFI") (class "Default")
      (node (ref "R27") (pin "2") (pinfunction "2_2") (pintype "passive"))
      (node (ref "R28") (pin "1") (pinfunction "1_1") (pintype "passive"))
    )
    (net (code "17") (name "/PMIC_INT_L") (class "Default")
      (node (ref "U6") (pin "7") (pinfunction "INT_7") (pintype "passive"))
    )
    (net (code "18") (name "/PMIC_PWRON") (class "Default")
      (node (ref "C83") (pin "1") (pinfunction "1_1") (pintype "passive"))
      (node (ref "U6") (pin "52") (pinfunction "PWRON_52") (pintype "passive"))
    )
    (net (code "19") (name "/PMIC_RESET_KEY") (class "Default")
      (node (ref "R31") (pin "1") (pinfunction "1_1") (pintype "passive"))
    )
    (net (code "20") (name "/PMIC_SLEEP_H") (class "Default")
      (node (ref "U6") (pin "49") (pinfunction "SLEEP_49") (pintype "passive"))
    )
    (net (code "21") (name "/RESETn") (class "Default")
      (node (ref "C85") (pin "2") (pinfunction "2_2") (pintype "passive"))
      (node (ref "R30") (pin "2") (pinfunction "2_2") (pintype "passive"))
      (node (ref "R31") (pin "2") (pinfunction "2_2") (pintype "passive"))
      (node (ref "U6") (pin "67") (pinfunction "RESETB_67") (pintype "passive"))
    )
    (net (code "22") (name "/SPKN_OUT") (class "Default")
      (node (ref "C78") (pin "2") (pinfunction "2_2") (pintype "passive"))
      (node (ref "L14") (pin "2") (pinfunction "2_2") (pintype "passive"))
    )
    (net (code "23") (name "/SPKP_OUT") (class "Default")
      (node (ref "C77") (pin "2") (pinfunction "2_2") (pintype "passive"))
      (node (ref "L16") (pin "2") (pinfunction "2_2") (pintype "passive"))
    )
    (net (code "24") (name "/USB_AVDD_0V9") (class "Default")
      (node (ref "L10") (pin "2") (pinfunction "2_2") (pintype "passive"))
    )
    (net (code "25") (name "/USB_AVDD_1V8") (class "Default")
      (node (ref "L12") (pin "2") (pinfunction "2_2") (pintype "passive"))
    )
    (net (code "26") (name "GND") (class "Default")
      (node (ref "C30") (pin "2") (pinfunction "2_2") (pintype "passive"))
      (node (ref "C31") (pin "2") (pinfunction "2_2") (pintype "passive"))
      (node (ref "C32") (pin "1") (pinfunction "1_1") (pintype "passive"))
      (node (ref "C33") (pin "1") (pinfunction "1_1") (pintype "passive"))
      (node (ref "C34") (pin "2") (pinfunction "2_2") (pintype "passive"))
      (node (ref "C35") (pin "2") (pinfunction "2_2") (pintype "passive"))
      (node (ref "C36") (pin "1") (pinfunction "1_1") (pintype "passive"))
      (node (ref "C37") (pin "2") (pinfunction "2_2") (pintype "passive"))
      (node (ref "C39") (pin "2") (pinfunction "2_2") (pintype "passive"))
      (node (ref "C40") (pin "2") (pinfunction "2_2") (pintype "passive"))
      (node (ref "C41") (pin "1") (pinfunction "1_1") (pintype "passive"))
      (node (ref "C43") (pin "1") (pinfunction "1_1") (pintype "passive"))
      (node (ref "C44") (pin "2") (pinfunction "2_2") (pintype "passive"))
      (node (ref "C45") (pin "2") (pinfunction "2_2") (pintype "passive"))
      (node (ref "C46") (pin "2") (pinfunction "2_2") (pintype "passive"))
      (node (ref "C47") (pin "1") (pinfunction "1_1") (pintype "passive"))
      (node (ref "C48") (pin "2") (pinfunction "2_2") (pintype "passive"))
      (node (ref "C49") (pin "1") (pinfunction "1_1") (pintype "passive"))
      (node (ref "C50") (pin "2") (pinfunction "2_2") (pintype "passive"))
      (node (ref "C51") (pin "1") (pinfunction "1_1") (pintype "passive"))
      (node (ref "C52") (pin "2") (pinfunction "2_2") (pintype "passive"))
      (node (ref "C53") (pin "2") (pinfunction "2_2") (pintype "passive"))
      (node (ref "C54") (pin "1") (pinfunction "1_1") (pintype "passive"))
      (node (ref "C56") (pin "2") (pinfunction "2_2") (pintype "passive"))
      (node (ref "C57") (pin "1") (pinfunction "1_1") (pintype "passive"))
      (node (ref "C58") (pin "2") (pinfunction "2_2") (pintype "passive"))
      (node (ref "C59") (pin "1") (pinfunction "1_1") (pintype "passive"))
      (node (ref "C60") (pin "1") (pinfunction "1_1") (pintype "passive"))
      (node (ref "C61") (pin "2") (pinfunction "2_2") (pintype "passive"))
      (node (ref "C62") (pin "1") (pinfunction "1_1") (pintype "passive"))
      (node (ref "C63") (pin "2") (pinfunction "2_2") (pintype "passive"))
      (node (ref "C64") (pin "1") (pinfunction "1_1") (pintype "passive"))
      (node (ref "C65") (pin "1") (pinfunction "1_1") (pintype "passive"))
      (node (ref "C66") (pin "1") (pinfunction "1_1") (pintype "passive"))
      (node (ref "C67") (pin "1") (pinfunction "1_1") (pintype "passive"))
      (node (ref "C69") (pin "1") (pinfunction "1_1") (pintype "passive"))
      (node (ref "C70") (pin "1") (pinfunction "1_1") (pintype "passive"))
      (node (ref "C71") (pin "1") (pinfunction "1_1") (pintype "passive"))
      (node (ref "C72") (pin "1") (pinfunction "1_1") (pintype "passive"))
      (node (ref "C73") (pin "1") (pinfunction "1_1") (pintype "passive"))
      (node (ref "C74") (pin "1") (pinfunction "1_1") (pintype "passive"))
      (node (ref "C75") (pin "2") (pinfunction "2_2") (pintype "passive"))
      (node (ref "C76") (pin "1") (pinfunction "1_1") (pintype "passive"))
      (node (ref "C77") (pin "1") (pinfunction "1_1") (pintype "passive"))
      (node (ref "C78") (pin "1") (pinfunction "1_1") (pintype "passive"))
      (node (ref "C80") (pin "1") (pinfunction "1_1") (pintype "passive"))
      (node (ref "C81") (pin "1") (pinfunction "1_1") (pintype "passive"))
      (node (ref "C82") (pin "1") (pinfunction "1_1") (pintype "passive"))
      (node (ref "C83") (pin "2") (pinfunction "2_2") (pintype "passive"))
      (node (ref "C85") (pin "1") (pinfunction "1_1") (pintype "passive"))
      (node (ref "R22") (pin "1") (pinfunction "1_1") (pintype "passive"))
      (node (ref "R24") (pin "2") (pinfunction "2_2") (pintype "passive"))
      (node (ref "R29") (pin "1") (pinfunction "1_1") (pintype "passive"))
      (node (ref "U6") (pin "47") (pinfunction "GNDREF_47") (pintype "passive"))
      (node (ref "U6") (pin "56") (pinfunction "BATDIV_56") (pintype "passive"))
      (node (ref "U6") (pin "62") (pinfunction "SNSP_62") (pintype "passive"))
      (node (ref "U6") (pin "63") (pinfunction "SNSN_63") (pintype "passive"))
      (node (ref "U6") (pin "69") (pinfunction "EPAD_69") (pintype "passive"))
    )
    (net (code "27") (name "Net-(U6A-FB3)") (class "Default")
      (node (ref "R21") (pin "2") (pinfunction "2_2") (pintype "passive"))
      (node (ref "R22") (pin "2") (pinfunction "2_2") (pintype "passive"))
      (node (ref "U6") (pin "27") (pinfunction "FB3_27") (pintype "passive"))
    )
    (net (code "28") (name "Net-(U6A-SW1)") (class "Default")
      (node (ref "L5") (pin "2") (pinfunction "2_2") (pintype "passive"))
      (node (ref "U6") (pin "12") (pinfunction "SW1_12") (pintype "passive"))
    )
    (net (code "29") (name "Net-(U6A-SW2)") (class "Default")
      (node (ref "L7") (pin "2") (pinfunction "2_2") (pintype "passive"))
      (node (ref "U6") (pin "9") (pinfunction "SW2_9") (pintype "passive"))
    )
    (net (code "30") (name "Net-(U6A-SW3)") (class "Default")
      (node (ref "L8") (pin "1") (pinfunction "1_1") (pintype "passive"))
      (node (ref "U6") (pin "25") (pinfunction "SW3_25") (pintype "passive"))
    )
    (net (code "31") (name "Net-(U6A-SW4)") (class "Default")
      (node (ref "L6") (pin "1") (pinfunction "1_1") (pintype "passive"))
      (node (ref "U6") (pin "65") (pinfunction "SW4_65") (pintype "passive"))
    )
    (net (code "32") (name "Net-(U6B-FB5)") (class "Default")
      (node (ref "R23") (pin "1") (pinfunction "1_1") (pintype "passive"))
      (node (ref "R24") (pin "1") (pinfunction "1_1") (pintype "passive"))
      (node (ref "U6") (pin "59") (pinfunction "FB5_59") (pintype "passive"))
    )
    (net (code "33") (name "Net-(U6B-SW5)") (class "Default")
      (node (ref "L9") (pin "1") (pinfunction "1_1") (pintype "passive"))
      (node (ref "U6") (pin "53") (pinfunction "SW5_53") (pintype "passive"))
    )
    (net (code "34") (name "Net-(U6C-CLK32K)") (class "Default")
      (node (ref "R28") (pin "2") (pinfunction "2_2") (pintype "passive"))
      (node (ref "U6") (pin "68") (pinfunction "CLK32K_68") (pintype "passive"))
    )
    (net (code "35") (name "Net-(U6C-VCC_RTC)") (class "Default")
      (node (ref "C63") (pin "1") (pinfunction "1_1") (pintype "passive"))
      (node (ref "R25") (pin "1") (pinfunction "1_1") (pintype "passive"))
      (node (ref "U6") (pin "45") (pinfunction "VCC_RTC_45") (pintype "passive"))
    )
    (net (code "36") (name "Net-(U6C-VDC)") (class "Default")
      (node (ref "C82") (pin "2") (pinfunction "2_2") (pintype "passive"))
      (node (ref "R26") (pin "1") (pinfunction "1_1") (pintype "passive"))
      (node (ref "R29") (pin "2") (pinfunction "2_2") (pintype "passive"))
      (node (ref "U6") (pin "61") (pinfunction "VDC_61") (pintype "passive"))
    )
    (net (code "37") (name "Net-(U6C-VREF)") (class "Default")
      (node (ref "C65") (pin "2") (pinfunction "2_2") (pintype "passive"))
      (node (ref "U6") (pin "46") (pinfunction "VREF_46") (pintype "passive"))
    )
    (net (code "38") (name "Net-(U6C-XIN)") (class "Default")
      (node (ref "C70") (pin "2") (pinfunction "2_2") (pintype "passive"))
      (node (ref "U6") (pin "50") (pinfunction "XIN_50") (pintype "passive"))
      (node (ref "X1") (pin "2") (pinfunction "2_2") (pintype "passive"))
    )
    (net (code "39") (name "Net-(U6C-XOUT)") (class "Default")
      (node (ref "C75") (pin "1") (pinfunction "1_1") (pintype "passive"))
      (node (ref "U6") (pin "51") (pinfunction "XOUT_51") (pintype "passive"))
      (node (ref "X1") (pin "1") (pinfunction "1_1") (pintype "passive"))
    )
    (net (code "40") (name "Net-(U6D-CPn)") (class "Default")
      (node (ref "C68") (pin "1") (pinfunction "1_1") (pintype "passive"))
      (node (ref "U6") (pin "36") (pinfunction "CPn_36") (pintype "passive"))
    )
    (net (code "41") (name "Net-(U6D-CPp)") (class "Default")
      (node (ref "C68") (pin "2") (pinfunction "2_2") (pintype "passive"))
      (node (ref "U6") (pin "37") (pinfunction "CPp_37") (pintype "passive"))
    )
    (net (code "42") (name "Net-(U6D-MIC1n)") (class "Default")
      (node (ref "C81") (pin "2") (pinfunction "2_2") (pintype "passive"))
      (node (ref "C84") (pin "1") (pinfunction "1_1") (pintype "passive"))
      (node (ref "U6") (pin "42") (pinfunction "MIC1n_42") (pintype "passive"))
    )
    (net (code "43") (name "Net-(U6D-MIC1p)") (class "Default")
      (node (ref "C79") (pin "1") (pinfunction "1_1") (pintype "passive"))
      (node (ref "C80") (pin "2") (pinfunction "2_2") (pintype "passive"))
      (node (ref "U6") (pin "43") (pinfunction "MIC1p_43") (pintype "passive"))
    )
    (net (code "44") (name "Net-(U6D-SPK_OUTn)") (class "Default")
      (node (ref "L14") (pin "1") (pinfunction "1_1") (pintype "passive"))
      (node (ref "U6") (pin "34") (pinfunction "SPK_OUTn_34") (pintype "passive"))
    )
    (net (code "45") (name "Net-(U6D-SPK_OUTp)") (class "Default")
      (node (ref "L16") (pin "1") (pinfunction "1_1") (pintype "passive"))
      (node (ref "U6") (pin "32") (pinfunction "SPK_OUTp_32") (pintype "passive"))
    )
    (net (code "46") (name "Net-(U6D-VCC_1P8A)") (class "Default")
      (node (ref "C76") (pin "2") (pinfunction "2_2") (pintype "passive"))
      (node (ref "U6") (pin "44") (pinfunction "VCC_1P8A_44") (pintype "passive"))
    )
    (net (code "47") (name "Net-(U6D-VCC_1P8D)") (class "Default")
      (node (ref "C74") (pin "2") (pinfunction "2_2") (pintype "passive"))
      (node (ref "U6") (pin "48") (pinfunction "VCC_1P8D_48") (pintype "passive"))
    )
    (net (code "48") (name "Net-(U6D-VCC_CPVDD)") (class "Default")
      (node (ref "C71") (pin "2") (pinfunction "2_2") (pintype "passive"))
      (node (ref "U6") (pin "38") (pinfunction "VCC_CPVDD_38") (pintype "passive"))
    )
    (net (code "49") (name "Net-(U6D-VCC_CPVSS)") (class "Default")
      (node (ref "C72") (pin "2") (pinfunction "2_2") (pintype "passive"))
      (node (ref "U6") (pin "35") (pinfunction "VCC_CPVSS_35") (pintype "passive"))
    )
    (net (code "50") (name "Net-(U6D-VCC_SPK_HP)") (class "Default")
      (node (ref "C67") (pin "2") (pinfunction "2_2") (pintype "passive"))
      (node (ref "L11") (pin "2") (pinfunction "2_2") (pintype "passive"))
      (node (ref "U6") (pin "33") (pinfunction "VCC_SPK_HP_33") (pintype "passive"))
    )
    (net (code "51") (name "VCC3V3_PMU") (class "Default")
      (node (ref "C45") (pin "1") (pinfunction "1_1") (pintype "passive"))
      (node (ref "R30") (pin "1") (pinfunction "1_1") (pintype "passive"))
      (node (ref "U6") (pin "31") (pinfunction "LDO6_31") (pintype "passive"))
    )
    (net (code "52") (name "VCC3V3_SD") (class "Default")
      (node (ref "C52") (pin "1") (pinfunction "1_1") (pintype "passive"))
      (node (ref "U6") (pin "58") (pinfunction "SWOUT2_58") (pintype "passive"))
    )
    (net (code "53") (name "VCC3V3_SYS") (class "Default")
      (node (ref "C31") (pin "1") (pinfunction "1_1") (pintype "passive"))
      (node (ref "C32") (pin "2") (pinfunction "2_2") (pintype "passive"))
      (node (ref "C33") (pin "2") (pinfunction "2_2") (pintype "passive"))
      (node (ref "C43") (pin "2") (pinfunction "2_2") (pintype "passive"))
      (node (ref "C47") (pin "2") (pinfunction "2_2") (pintype "passive"))
      (node (ref "C49") (pin "2") (pinfunction "2_2") (pintype "passive"))
      (node (ref "C54") (pin "2") (pinfunction "2_2") (pintype "passive"))
      (node (ref "C59") (pin "2") (pinfunction "2_2") (pintype "passive"))
      (node (ref "U6") (pin "10") (pinfunction "VCC2_10") (pintype "passive"))
      (node (ref "U6") (pin "11") (pinfunction "VCC1_11") (pintype "passive"))
      (node (ref "U6") (pin "22") (pinfunction "VCC5_22") (pintype "passive"))
      (node (ref "U6") (pin "24") (pinfunction "VCC3_24") (pintype "passive"))
      (node (ref "U6") (pin "30") (pinfunction "VCC6_30") (pintype "passive"))
      (node (ref "U6") (pin "4") (pinfunction "VCC7_4") (pintype "passive"))
      (node (ref "U6") (pin "54") (pinfunction "VCC9_54") (pintype "passive"))
      (node (ref "U6") (pin "57") (pinfunction "VCC8_57") (pintype "passive"))
      (node (ref "U6") (pin "66") (pinfunction "VCC4_66") (pintype "passive"))
    )
    (net (code "54") (name "VCC5V0_SYS") (class "Default")
      (node (ref "L11") (pin "1") (pinfunction "1_1") (pintype "passive"))
      (node (ref "R25") (pin "2") (pinfunction "2_2") (pintype "passive"))
      (node (ref "R26") (pin "2") (pinfunction "2_2") (pintype "passive"))
    )
    (net (code "55") (name "VCCA1V8_IMAGE") (class "Default")
      (node (ref "C50") (pin "1") (pinfunction "1_1") (pintype "passive"))
      (node (ref "C73") (pin "2") (pinfunction "2_2") (pintype "passive"))
      (node (ref "L15") (pin "1") (pinfunction "1_1") (pintype "passive"))
      (node (ref "U6") (pin "6") (pinfunction "LDO9_6") (pintype "passive"))
    )
    (net (code "56") (name "VCCA1V8_PMU") (class "Default")
      (node (ref "C48") (pin "1") (pinfunction "1_1") (pintype "passive"))
      (node (ref "U6") (pin "5") (pinfunction "LDO8_5") (pintype "passive"))
    )
    (net (code "57") (name "VCCA_1V8") (class "Default")
      (node (ref "C46") (pin "1") (pinfunction "1_1") (pintype "passive"))
      (node (ref "C66") (pin "2") (pinfunction "2_2") (pintype "passive"))
      (node (ref "L12") (pin "1") (pinfunction "1_1") (pintype "passive"))
      (node (ref "U6") (pin "3") (pinfunction "LDO7_3") (pintype "passive"))
    )
    (net (code "58") (name "VCCIO_ACODEC") (class "Default")
      (node (ref "C37") (pin "1") (pinfunction "1_1") (pintype "passive"))
      (node (ref "U6") (pin "28") (pinfunction "LDO4_28") (pintype "passive"))
    )
    (net (code "59") (name "VCCIO_SD") (class "Default")
      (node (ref "C44") (pin "1") (pinfunction "1_1") (pintype "passive"))
      (node (ref "U6") (pin "29") (pinfunction "LDO5_29") (pintype "passive"))
    )
    (net (code "60") (name "VCCIO_WL") (class "Default")
      (node (ref "C60") (pin "2") (pinfunction "2_2") (pintype "passive"))
      (node (ref "R18") (pin "2") (pinfunction "2_2") (pintype "passive"))
      (node (ref "R20") (pin "2") (pinfunction "2_2") (pintype "passive"))
      (node (ref "R27") (pin "1") (pinfunction "1_1") (pintype "passive"))
    )
    (net (code "61") (name "VCC_1V8") (class "Default")
      (node (ref "C61") (pin "1") (pinfunction "1_1") (pintype "passive"))
      (node (ref "C62") (pin "2") (pinfunction "2_2") (pintype "passive"))
      (node (ref "L9") (pin "2") (pinfunction "2_2") (pintype "passive"))
      (node (ref "R18") (pin "1") (pinfunction "1_1") (pintype "passive"))
      (node (ref "R23") (pin "2") (pinfunction "2_2") (pintype "passive"))
    )
    (net (code "62") (name "VCC_3V3") (class "Default")
      (node (ref "C58") (pin "1") (pinfunction "1_1") (pintype "passive"))
      (node (ref "R20") (pin "1") (pinfunction "1_1") (pintype "passive"))
      (node (ref "U6") (pin "55") (pinfunction "SWOUT1_55") (pintype "passive"))
    )
    (net (code "63") (name "VCC_DDR") (class "Default")
      (node (ref "C56") (pin "1") (pinfunction "1_1") (pintype "passive"))
      (node (ref "C57") (pin "2") (pinfunction "2_2") (pintype "passive"))
      (node (ref "L8") (pin "2") (pinfunction "2_2") (pintype "passive"))
      (node (ref "R21") (pin "1") (pinfunction "1_1") (pintype "passive"))
      (node (ref "U6") (pin "26") (pinfunction "VBUCK3_26") (pintype "passive"))
    )
    (net (code "64") (name "VDDA0V9_IMAGE") (class "Default")
      (node (ref "C30") (pin "1") (pinfunction "1_1") (pintype "passive"))
      (node (ref "C69") (pin "2") (pinfunction "2_2") (pintype "passive"))
      (node (ref "L13") (pin "1") (pinfunction "1_1") (pintype "passive"))
      (node (ref "U6") (pin "23") (pinfunction "LDO1_23") (pintype "passive"))
    )
    (net (code "65") (name "VDDA0V9_PMU") (class "Default")
      (node (ref "C35") (pin "1") (pinfunction "1_1") (pintype "passive"))
      (node (ref "U6") (pin "20") (pinfunction "LDO3_20") (pintype "passive"))
    )
    (net (code "66") (name "VDDA_0V9") (class "Default")
      (node (ref "C34") (pin "1") (pinfunction "1_1") (pintype "passive"))
      (node (ref "C64") (pin "2") (pinfunction "2_2") (pintype "passive"))
      (node (ref "L10") (pin "1") (pinfunction "1_1") (pintype "passive"))
      (node (ref "U6") (pin "21") (pinfunction "LDO2_21") (pintype "passive"))
    )
    (net (code "67") (name "VDD_GPU") (class "Default")
      (node (ref "C51") (pin "2") (pinfunction "2_2") (pintype "passive"))
      (node (ref "C53") (pin "1") (pinfunction "1_1") (pintype "passive"))
      (node (ref "C55") (pin "1") (pinfunction "1_1") (pintype "passive"))
      (node (ref "C55") (pin "2") (pinfunction "2_2") (pintype "passive"))
      (node (ref "L7") (pin "1") (pinfunction "1_1") (pintype "passive"))
      (node (ref "R19") (pin "1") (pinfunction "1_1") (pintype "passive"))
      (node (ref "R19") (pin "2") (pinfunction "2_2") (pintype "passive"))
      (node (ref "U6") (pin "8") (pinfunction "FB2_8") (pintype "passive"))
    )
    (net (code "68") (name "VDD_LOGIC") (class "Default")
      (node (ref "C36") (pin "2") (pinfunction "2_2") (pintype "passive"))
      (node (ref "C38") (pin "1") (pinfunction "1_1") (pintype "passive"))
      (node (ref "C38") (pin "2") (pinfunction "2_2") (pintype "passive"))
      (node (ref "C39") (pin "1") (pinfunction "1_1") (pintype "passive"))
      (node (ref "L5") (pin "1") (pinfunction "1_1") (pintype "passive"))
      (node (ref "R17") (pin "1") (pinfunction "1_1") (pintype "passive"))
      (node (ref "R17") (pin "2") (pinfunction "2_2") (pintype "passive"))
      (node (ref "U6") (pin "13") (pinfunction "FB1_13") (pintype "passive"))
    )
    (net (code "69") (name "VDD_NPU") (class "Default")
      (node (ref "C40") (pin "1") (pinfunction "1_1") (pintype "passive"))
      (node (ref "C41") (pin "2") (pinfunction "2_2") (pintype "passive"))
      (node (ref "C42") (pin "1") (pinfunction "1_1") (pintype "passive"))
      (node (ref "C42") (pin "2") (pinfunction "2_2") (pintype "passive"))
      (node (ref "L6") (pin "2") (pinfunction "2_2") (pintype "passive"))
      (node (ref "R16") (pin "1") (pinfunction "1_1") (pintype "passive"))
      (node (ref "R16") (pin "2") (pinfunction "2_2") (pintype "passive"))
      (node (ref "U6") (pin "64") (pinfunction "FB4_64") (pintype "passive"))
    )
    (net (code "70") (name "unconnected-(U6C-EXT_EN-Pad60)") (class "Default")
      (node (ref "U6") (pin "60") (pinfunction "EXT_EN_60") (pintype "passive+no_connect"))
    )
  )
)
